# Espectrometro_Micro.net
KiCad netlist of a schematic drawn in Altium Designer
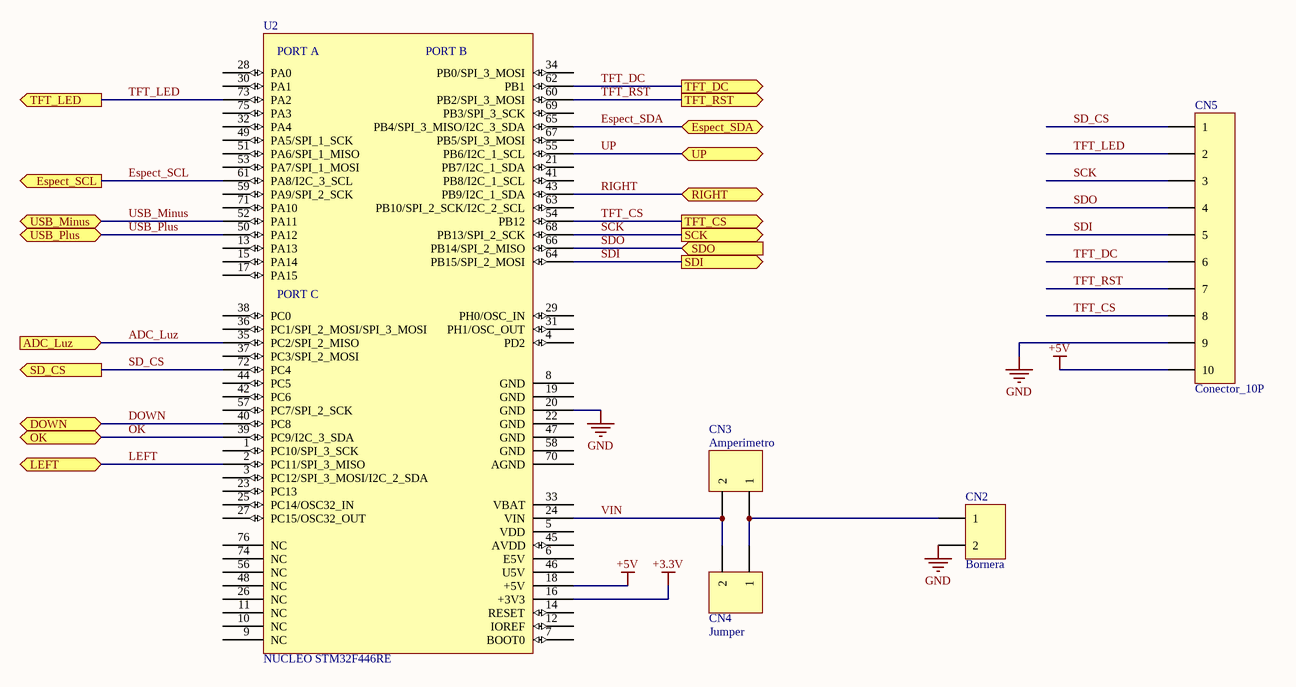
[diagram p0: Espectrometro_Micro.SchDoc]

(export (version "E")
  (design (tool "Eeschema 10.0.6"))
  (components
    (comp (ref "CN2")
      (value "Bornera")
      (footprint "TERMINAL BLOCK DG306 - D5mm - 02P")
      (description "Conector 2 Vias")
      (libsource (lib "") (part "Conector_2P_1"))
    )
    (comp (ref "CN3")
      (value "Amperimetro")
      (footprint "TERMINAL BLOCK DG306 - D5mm - 02P")
      (description "Conector 2 Vias")
      (libsource (lib "Nucleo") (part "Conector_2P_Amp"))
    )
    (comp (ref "CN4")
      (value "Jumper")
      (footprint "HEADER_M-2x1_0.1\"_V")
      (libsource (lib "Nucleo") (part "Conector_2P"))
    )
    (comp (ref "CN5")
      (value "Conector_10P")
      (footprint "HEADER_M-10x2_0.1\"_V")
      (description "Conector 10 Vias")
      (libsource (lib "Nucleo") (part "Conector_10P"))
    )
    (comp (ref "U2")
      (value "NUCLEO STM32F446RE")
      (footprint "NUCLEO - STM32F446RE - UP")
      (libsource (lib "Nucleo") (part "NUCLEO STM32F446RE"))
    )
  )
  (nets
    (net (code "1") (name "+3.3V") (class "Default")
      (node (ref "U2") (pin "16") (pinfunction "+3V3_16") (pintype "passive"))
    )
    (net (code "2") (name "+5V") (class "Default")
      (node (ref "CN5") (pin "10") (pinfunction "10_10") (pintype "passive"))
      (node (ref "U2") (pin "18") (pinfunction "+5V_18") (pintype "passive"))
    )
    (net (code "3") (name "/ADC_Luz") (class "Default")
      (node (ref "U2") (pin "35") (pinfunction "PC2/SPI_2_MISO_35") (pintype "bidirectional"))
    )
    (net (code "4") (name "/DOWN") (class "Default")
      (node (ref "U2") (pin "40") (pinfunction "PC8_40") (pintype "bidirectional"))
    )
    (net (code "5") (name "/Espect_SCL") (class "Default")
      (node (ref "U2") (pin "61") (pinfunction "PA8/I2C_3_SCL_61") (pintype "bidirectional"))
    )
    (net (code "6") (name "/Espect_SDA") (class "Default")
      (node (ref "U2") (pin "65") (pinfunction "PB4/SPI_3_MISO/I2C_3_SDA_65") (pintype "bidirectional"))
    )
    (net (code "7") (name "/LEFT") (class "Default")
      (node (ref "U2") (pin "2") (pinfunction "PC11/SPI_3_MISO_2") (pintype "bidirectional"))
    )
    (net (code "8") (name "/OK") (class "Default")
      (node (ref "U2") (pin "39") (pinfunction "PC9/I2C_3_SDA_39") (pintype "bidirectional"))
    )
    (net (code "9") (name "/RIGHT") (class "Default")
      (node (ref "U2") (pin "43") (pinfunction "PB9/I2C_1_SDA_43") (pintype "bidirectional"))
    )
    (net (code "10") (name "/SCK") (class "Default")
      (node (ref "CN5") (pin "3") (pinfunction "3_3") (pintype "passive"))
      (node (ref "U2") (pin "68") (pinfunction "PB13/SPI_2_SCK_68") (pintype "bidirectional"))
    )
    (net (code "11") (name "/SDI") (class "Default")
      (node (ref "CN5") (pin "5") (pinfunction "5_5") (pintype "passive"))
      (node (ref "U2") (pin "64") (pinfunction "PB15/SPI_2_MOSI_64") (pintype "bidirectional"))
    )
    (net (code "12") (name "/SDO") (class "Default")
      (node (ref "CN5") (pin "4") (pinfunction "4_4") (pintype "passive"))
      (node (ref "U2") (pin "66") (pinfunction "PB14/SPI_2_MISO_66") (pintype "bidirectional"))
    )
    (net (code "13") (name "/SD_CS") (class "Default")
      (node (ref "CN5") (pin "1") (pinfunction "1_1") (pintype "passive"))
      (node (ref "U2") (pin "72") (pinfunction "PC4_72") (pintype "bidirectional"))
    )
    (net (code "14") (name "/TFT_CS") (class "Default")
      (node (ref "CN5") (pin "8") (pinfunction "8_8") (pintype "passive"))
      (node (ref "U2") (pin "54") (pinfunction "PB12_54") (pintype "bidirectional"))
    )
    (net (code "15") (name "/TFT_DC") (class "Default")
      (node (ref "CN5") (pin "6") (pinfunction "6_6") (pintype "passive"))
      (node (ref "U2") (pin "62") (pinfunction "PB1_62") (pintype "bidirectional"))
    )
    (net (code "16") (name "/TFT_LED") (class "Default")
      (node (ref "CN5") (pin "2") (pinfunction "2_2") (pintype "passive"))
      (node (ref "U2") (pin "73") (pinfunction "PA2_73") (pintype "bidirectional"))
    )
    (net (code "17") (name "/TFT_RST") (class "Default")
      (node (ref "CN5") (pin "7") (pinfunction "7_7") (pintype "passive"))
      (node (ref "U2") (pin "60") (pinfunction "PB2/SPI_3_MOSI_60") (pintype "bidirectional"))
    )
    (net (code "18") (name "/UP") (class "Default")
      (node (ref "U2") (pin "55") (pinfunction "PB6/I2C_1_SCL_55") (pintype "bidirectional"))
    )
    (net (code "19") (name "/USB_Minus") (class "Default")
      (node (ref "U2") (pin "52") (pinfunction "PA11_52") (pintype "bidirectional"))
    )
    (net (code "20") (name "/USB_Plus") (class "Default")
      (node (ref "U2") (pin "50") (pinfunction "PA12_50") (pintype "bidirectional"))
    )
    (net (code "21") (name "/VIN") (class "Default")
      (node (ref "CN3") (pin "2") (pinfunction "2_2") (pintype "passive"))
      (node (ref "CN4") (pin "2") (pinfunction "2_2") (pintype "passive"))
      (node (ref "U2") (pin "24") (pinfunction "VIN_24") (pintype "passive"))
    )
    (net (code "22") (name "GND") (class "Default")
      (node (ref "CN2") (pin "2") (pinfunction "2_2") (pintype "passive"))
      (node (ref "CN5") (pin "9") (pinfunction "9_9") (pintype "passive"))
      (node (ref "U2") (pin "20") (pinfunction "GND_20") (pintype "passive"))
    )
    (net (code "23") (name "Net-(CN2-Pad1)") (class "Default")
      (node (ref "CN2") (pin "1") (pinfunction "1_1") (pintype "passive"))
      (node (ref "CN3") (pin "1") (pinfunction "1_1") (pintype "passive"))
      (node (ref "CN4") (pin "1") (pinfunction "1_1") (pintype "passive"))
    )
    (net (code "24") (name "unconnected-(U2-AGND-Pad70)") (class "Default")
      (node (ref "U2") (pin "70") (pinfunction "AGND_70") (pintype "passive"))
    )
    (net (code "25") (name "unconnected-(U2-AVDD-Pad45)") (class "Default")
      (node (ref "U2") (pin "45") (pinfunction "AVDD_45") (pintype "bidirectional"))
    )
    (net (code "26") (name "unconnected-(U2-BOOT0-Pad7)") (class "Default")
      (node (ref "U2") (pin "7") (pinfunction "BOOT0_7") (pintype "bidirectional"))
    )
    (net (code "27") (name "unconnected-(U2-E5V-Pad6)") (class "Default")
      (node (ref "U2") (pin "6") (pinfunction "E5V_6") (pintype "passive"))
    )
    (net (code "28") (name "unconnected-(U2-GND-Pad8)") (class "Default")
      (node (ref "U2") (pin "8") (pinfunction "GND_8") (pintype "passive"))
    )
    (net (code "29") (name "unconnected-(U2-GND-Pad19)") (class "Default")
      (node (ref "U2") (pin "19") (pinfunction "GND_19") (pintype "passive"))
    )
    (net (code "30") (name "unconnected-(U2-GND-Pad22)") (class "Default")
      (node (ref "U2") (pin "22") (pinfunction "GND_22") (pintype "passive"))
    )
    (net (code "31") (name "unconnected-(U2-GND-Pad47)") (class "Default")
      (node (ref "U2") (pin "47") (pinfunction "GND_47") (pintype "passive"))
    )
    (net (code "32") (name "unconnected-(U2-GND-Pad58)") (class "Default")
      (node (ref "U2") (pin "58") (pinfunction "GND_58") (pintype "passive"))
    )
    (net (code "33") (name "unconnected-(U2-IOREF-Pad12)") (class "Default")
      (node (ref "U2") (pin "12") (pinfunction "IOREF_12") (pintype "bidirectional"))
    )
    (net (code "34") (name "unconnected-(U2-NC-Pad9)") (class "Default")
      (node (ref "U2") (pin "9") (pinfunction "NC_9") (pintype "passive"))
    )
    (net (code "35") (name "unconnected-(U2-NC-Pad10)") (class "Default")
      (node (ref "U2") (pin "10") (pinfunction "NC_10") (pintype "passive"))
    )
    (net (code "36") (name "unconnected-(U2-NC-Pad11)") (class "Default")
      (node (ref "U2") (pin "11") (pinfunction "NC_11") (pintype "passive"))
    )
    (net (code "37") (name "unconnected-(U2-NC-Pad26)") (class "Default")
      (node (ref "U2") (pin "26") (pinfunction "NC_26") (pintype "passive"))
    )
    (net (code "38") (name "unconnected-(U2-NC-Pad48)") (class "Default")
      (node (ref "U2") (pin "48") (pinfunction "NC_48") (pintype "passive"))
    )
    (net (code "39") (name "unconnected-(U2-NC-Pad56)") (class "Default")
      (node (ref "U2") (pin "56") (pinfunction "NC_56") (pintype "passive"))
    )
    (net (code "40") (name "unconnected-(U2-NC-Pad74)") (class "Default")
      (node (ref "U2") (pin "74") (pinfunction "NC_74") (pintype "passive"))
    )
    (net (code "41") (name "unconnected-(U2-NC-Pad76)") (class "Default")
      (node (ref "U2") (pin "76") (pinfunction "NC_76") (pintype "passive"))
    )
    (net (code "42") (name "unconnected-(U2-PA0-Pad28)") (class "Default")
      (node (ref "U2") (pin "28") (pinfunction "PA0_28") (pintype "bidirectional"))
    )
    (net (code "43") (name "unconnected-(U2-PA1-Pad30)") (class "Default")
      (node (ref "U2") (pin "30") (pinfunction "PA1_30") (pintype "bidirectional"))
    )
    (net (code "44") (name "unconnected-(U2-PA3-Pad75)") (class "Default")
      (node (ref "U2") (pin "75") (pinfunction "PA3_75") (pintype "bidirectional"))
    )
    (net (code "45") (name "unconnected-(U2-PA4-Pad32)") (class "Default")
      (node (ref "U2") (pin "32") (pinfunction "PA4_32") (pintype "bidirectional"))
    )
    (net (code "46") (name "unconnected-(U2-PA5{slash}SPI_1_SCK-Pad49)") (class "Default")
      (node (ref "U2") (pin "49") (pinfunction "PA5/SPI_1_SCK_49") (pintype "bidirectional"))
    )
    (net (code "47") (name "unconnected-(U2-PA6{slash}SPI_1_MISO-Pad51)") (class "Default")
      (node (ref "U2") (pin "51") (pinfunction "PA6/SPI_1_MISO_51") (pintype "bidirectional"))
    )
    (net (code "48") (name "unconnected-(U2-PA7{slash}SPI_1_MOSI-Pad53)") (class "Default")
      (node (ref "U2") (pin "53") (pinfunction "PA7/SPI_1_MOSI_53") (pintype "bidirectional"))
    )
    (net (code "49") (name "unconnected-(U2-PA9{slash}SPI_2_SCK-Pad59)") (class "Default")
      (node (ref "U2") (pin "59") (pinfunction "PA9/SPI_2_SCK_59") (pintype "bidirectional"))
    )
    (net (code "50") (name "unconnected-(U2-PA10-Pad71)") (class "Default")
      (node (ref "U2") (pin "71") (pinfunction "PA10_71") (pintype "bidirectional"))
    )
    (net (code "51") (name "unconnected-(U2-PA13-Pad13)") (class "Default")
      (node (ref "U2") (pin "13") (pinfunction "PA13_13") (pintype "bidirectional"))
    )
    (net (code "52") (name "unconnected-(U2-PA14-Pad15)") (class "Default")
      (node (ref "U2") (pin "15") (pinfunction "PA14_15") (pintype "bidirectional"))
    )
    (net (code "53") (name "unconnected-(U2-PA15-Pad17)") (class "Default")
      (node (ref "U2") (pin "17") (pinfunction "PA15_17") (pintype "bidirectional"))
    )
    (net (code "54") (name "unconnected-(U2-PB0{slash}SPI_3_MOSI-Pad34)") (class "Default")
      (node (ref "U2") (pin "34") (pinfunction "PB0/SPI_3_MOSI_34") (pintype "bidirectional"))
    )
    (net (code "55") (name "unconnected-(U2-PB3{slash}SPI_3_SCK-Pad69)") (class "Default")
      (node (ref "U2") (pin "69") (pinfunction "PB3/SPI_3_SCK_69") (pintype "bidirectional"))
    )
    (net (code "56") (name "unconnected-(U2-PB5{slash}SPI_3_MOSI-Pad67)") (class "Default")
      (node (ref "U2") (pin "67") (pinfunction "PB5/SPI_3_MOSI_67") (pintype "bidirectional"))
    )
    (net (code "57") (name "unconnected-(U2-PB7{slash}I2C_1_SDA-Pad21)") (class "Default")
      (node (ref "U2") (pin "21") (pinfunction "PB7/I2C_1_SDA_21") (pintype "bidirectional"))
    )
    (net (code "58") (name "unconnected-(U2-PB8{slash}I2C_1_SCL-Pad41)") (class "Default")
      (node (ref "U2") (pin "41") (pinfunction "PB8/I2C_1_SCL_41") (pintype "bidirectional"))
    )
    (net (code "59") (name "unconnected-(U2-PB10{slash}SPI_2_SCK{slash}I2C_2_SCL-Pad63)") (class "Default")
      (node (ref "U2") (pin "63") (pinfunction "PB10/SPI_2_SCK/I2C_2_SCL_63") (pintype "bidirectional"))
    )
    (net (code "60") (name "unconnected-(U2-PC0-Pad38)") (class "Default")
      (node (ref "U2") (pin "38") (pinfunction "PC0_38") (pintype "bidirectional"))
    )
    (net (code "61") (name "unconnected-(U2-PC1{slash}SPI_2_MOSI{slash}SPI_3_MOSI-Pad36)") (class "Default")
      (node (ref "U2") (pin "36") (pinfunction "PC1/SPI_2_MOSI/SPI_3_MOSI_36") (pintype "bidirectional"))
    )
    (net (code "62") (name "unconnected-(U2-PC3{slash}SPI_2_MOSI-Pad37)") (class "Default")
      (node (ref "U2") (pin "37") (pinfunction "PC3/SPI_2_MOSI_37") (pintype "bidirectional"))
    )
    (net (code "63") (name "unconnected-(U2-PC5-Pad44)") (class "Default")
      (node (ref "U2") (pin "44") (pinfunction "PC5_44") (pintype "bidirectional"))
    )
    (net (code "64") (name "unconnected-(U2-PC6-Pad42)") (class "Default")
      (node (ref "U2") (pin "42") (pinfunction "PC6_42") (pintype "bidirectional"))
    )
    (net (code "65") (name "unconnected-(U2-PC7{slash}SPI_2_SCK-Pad57)") (class "Default")
      (node (ref "U2") (pin "57") (pinfunction "PC7/SPI_2_SCK_57") (pintype "bidirectional"))
    )
    (net (code "66") (name "unconnected-(U2-PC10{slash}SPI_3_SCK-Pad1)") (class "Default")
      (node (ref "U2") (pin "1") (pinfunction "PC10/SPI_3_SCK_1") (pintype "bidirectional"))
    )
    (net (code "67") (name "unconnected-(U2-PC12{slash}SPI_3_MOSI{slash}I2C_2_SDA-Pad3)") (class "Default")
      (node (ref "U2") (pin "3") (pinfunction "PC12/SPI_3_MOSI/I2C_2_SDA_3") (pintype "bidirectional"))
    )
    (net (code "68") (name "unconnected-(U2-PC13-Pad23)") (class "Default")
      (node (ref "U2") (pin "23") (pinfunction "PC13_23") (pintype "bidirectional"))
    )
    (net (code "69") (name "unconnected-(U2-PC14{slash}OSC32_IN-Pad25)") (class "Default")
      (node (ref "U2") (pin "25") (pinfunction "PC14/OSC32_IN_25") (pintype "bidirectional"))
    )
    (net (code "70") (name "unconnected-(U2-PC15{slash}OSC32_OUT-Pad27)") (class "Default")
      (node (ref "U2") (pin "27") (pinfunction "PC15/OSC32_OUT_27") (pintype "bidirectional"))
    )
    (net (code "71") (name "unconnected-(U2-PD2-Pad4)") (class "Default")
      (node (ref "U2") (pin "4") (pinfunction "PD2_4") (pintype "bidirectional"))
    )
    (net (code "72") (name "unconnected-(U2-PH0{slash}OSC_IN-Pad29)") (class "Default")
      (node (ref "U2") (pin "29") (pinfunction "PH0/OSC_IN_29") (pintype "bidirectional"))
    )
    (net (code "73") (name "unconnected-(U2-PH1{slash}OSC_OUT-Pad31)") (class "Default")
      (node (ref "U2") (pin "31") (pinfunction "PH1/OSC_OUT_31") (pintype "bidirectional"))
    )
    (net (code "74") (name "unconnected-(U2-RESET-Pad14)") (class "Default")
      (node (ref "U2") (pin "14") (pinfunction "RESET_14") (pintype "bidirectional"))
    )
    (net (code "75") (name "unconnected-(U2-U5V-Pad46)") (class "Default")
      (node (ref "U2") (pin "46") (pinfunction "U5V_46") (pintype "passive"))
    )
    (net (code "76") (name "unconnected-(U2-VBAT-Pad33)") (class "Default")
      (node (ref "U2") (pin "33") (pinfunction "VBAT_33") (pintype "passive"))
    )
    (net (code "77") (name "unconnected-(U2-VDD-Pad5)") (class "Default")
      (node (ref "U2") (pin "5") (pinfunction "VDD_5") (pintype "passive"))
    )
  )
)
